# LM2596.net
KiCad netlist of a schematic drawn in Altium Designer
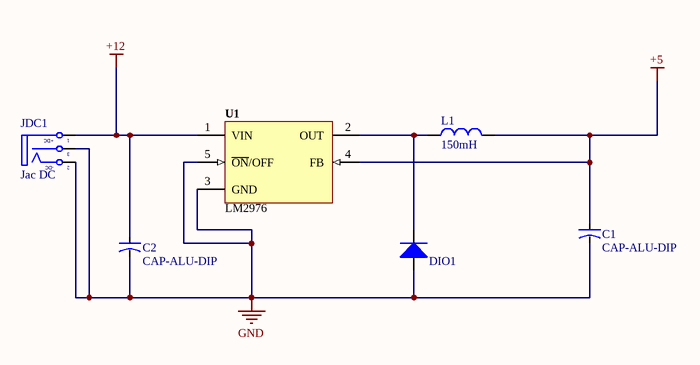
[diagram p0: LM2596.SchDoc]

(export (version "E")
  (design (tool "Eeschema 10.0.6"))
  (components
    (comp (ref "C1")
      (value "CAP-ALU-DIP")
      (footprint "CA-ALU-2.54")
      (description "Capacitor (Semiconductor SIM Model)")
      (fields (field (name "PUBLISHER") "Altium Limited"))
      (libsource (lib "My Library") (part "CAP-ALU-DIP"))
    )
    (comp (ref "C2")
      (value "CAP-ALU-DIP")
      (footprint "CA-ALU-2.54")
      (description "Capacitor (Semiconductor SIM Model)")
      (fields (field (name "PUBLISHER") "Altium Limited"))
      (libsource (lib "My Library") (part "CAP-ALU-DIP"))
    )
    (comp (ref "DIO1")
      (value "Diode SMD")
      (footprint "DIO-SMD-106")
      (description "Default Diode")
      (fields (field (name "PUBLISHER") "Altium Limited"))
      (libsource (lib "My Library") (part "Diode SMD"))
    )
    (comp (ref "JDC1")
      (value "Jac DC")
      (footprint "DC-IN")
      (description "Jac DC input")
      (libsource (lib "My Library") (part "DCIN"))
    )
    (comp (ref "L1")
      (value "150mH")
      (footprint "L-SMD-M-7.3x4.5")
      (description "Inductor")
      (libsource (lib "My Library") (part "Inductor"))
    )
    (comp (ref "U1") (value "LM2976") (footprint "TO-263") (libsource (lib "My Library") (part "LM2596")))
  )
  (nets
    (net (code "1") (name "+5") (class "Default")
      (node (ref "C1") (pin "1") (pinfunction "1_1") (pintype "passive"))
      (node (ref "L1") (pin "2") (pinfunction "2_2") (pintype "passive"))
      (node (ref "U1") (pin "4") (pinfunction "FB_4") (pintype "input"))
    )
    (net (code "2") (name "+12") (class "Default")
      (node (ref "C2") (pin "1") (pinfunction "1_1") (pintype "passive"))
      (node (ref "JDC1") (pin "1") (pinfunction "T_1") (pintype "passive"))
      (node (ref "U1") (pin "1") (pinfunction "VIN_1") (pintype "power_in"))
    )
    (net (code "3") (name "GND") (class "Default")
      (node (ref "C1") (pin "2") (pinfunction "2_2") (pintype "passive"))
      (node (ref "C2") (pin "2") (pinfunction "2_2") (pintype "passive"))
      (node (ref "DIO1") (pin "1") (pinfunction "A_1") (pintype "passive"))
      (node (ref "JDC1") (pin "2") (pinfunction "TN_2") (pintype "passive"))
      (node (ref "JDC1") (pin "3") (pinfunction "S_3") (pintype "power_in"))
      (node (ref "U1") (pin "3") (pinfunction "GND_3") (pintype "power_in"))
      (node (ref "U1") (pin "5") (pinfunction "~{ON}/OFF_5") (pintype "input"))
    )
    (net (code "4") (name "Net-(DIO1-K)") (class "Default")
      (node (ref "DIO1") (pin "2") (pinfunction "K_2") (pintype "passive"))
      (node (ref "L1") (pin "1") (pinfunction "1_1") (pintype "passive"))
      (node (ref "U1") (pin "2") (pinfunction "OUT_2") (pintype "power_in"))
    )
  )
)
